# CAN_PHY.net
KiCad netlist of a schematic drawn in Altium Designer
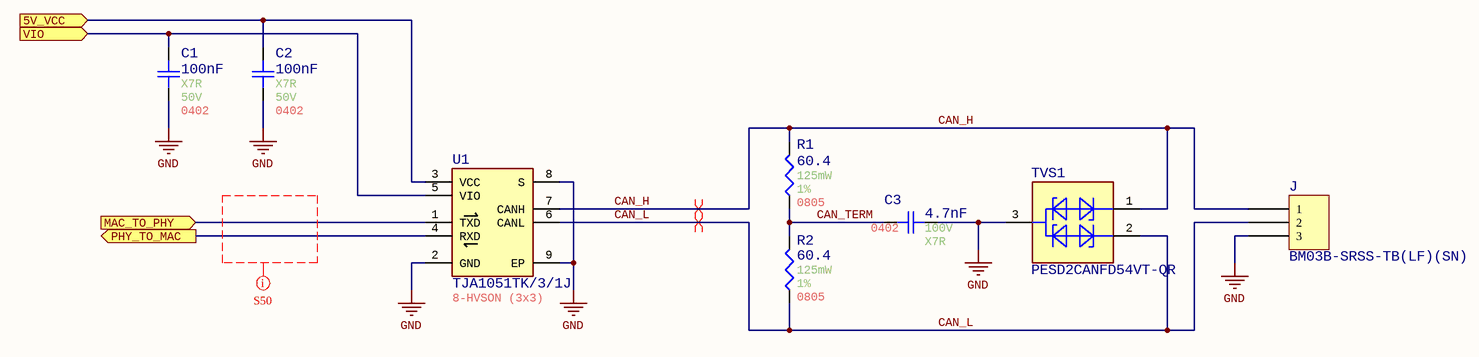
[diagram p0: CAN_PHY.SchDoc]

(export (version "E")
  (design (tool "Eeschema 10.0.6"))
  (components
    (comp (ref "C1")
      (value "100nF")
      (footprint "Generic 0402 capacitor")
      (fields
        (field (name "TEMPERATURE COEFFICIENT") "X7R")
        (field (name "VOLTAGE RATING") "50V")
        (field (name "CASE/PACKAGE") "0402")
        (field (name "TOLERANCE") "10%")
        (field (name "Comment") "GRT155R71H104KE01D")
      )
      (libsource (lib "Raise Robotics") (part "Unpolarized Capacitor"))
    )
    (comp (ref "C2")
      (value "100nF")
      (footprint "Generic 0402 capacitor")
      (fields
        (field (name "TEMPERATURE COEFFICIENT") "X7R")
        (field (name "VOLTAGE RATING") "50V")
        (field (name "CASE/PACKAGE") "0402")
        (field (name "TOLERANCE") "10%")
        (field (name "Comment") "GRT155R71H104KE01D")
      )
      (libsource (lib "Raise Robotics") (part "Unpolarized Capacitor"))
    )
    (comp (ref "C3")
      (value "4.7nF")
      (footprint "Generic 0402 capacitor")
      (fields
        (field (name "TEMPERATURE COEFFICIENT") "X7R")
        (field (name "VOLTAGE RATING") "100V")
        (field (name "CASE/PACKAGE") "0402")
        (field (name "TOLERANCE") "10%")
        (field (name "Comment") "GCM155R72A472KA37D")
      )
      (libsource (lib "Raise Robotics") (part "Unpolarized Capacitor"))
    )
    (comp (ref "J")
      (value "BM03B-SRSS-TB(LF)(SN)")
      (footprint "JST BM03B-SRSS-TB")
      (description "CONN HEADER SMD 3POS 1MM")
      (fields (field (name "MANUFACTURER") "JST Sales America Inc."))
      (libsource (lib "Celestial Altium Library - altium_library") (part "3 Pin"))
    )
    (comp (ref "R1")
      (value "60.4")
      (footprint "0805 Resistor")
      (description "Res 60.4 Ohm 1% 1/8W 0805")
      (fields
        (field (name "POWER") "125mW")
        (field (name "TOLERANCE") "1%")
        (field (name "CASE/PACKAGE") "0805")
        (field (name "MANUFACTURER PART NUMBER") "TFA0805R60R4F-T5")
      )
      (libsource (lib "Raise Robotics") (part "Resistor"))
    )
    (comp (ref "R2")
      (value "60.4")
      (footprint "0805 Resistor")
      (description "Res 60.4 Ohm 1% 1/8W 0805")
      (fields
        (field (name "POWER") "125mW")
        (field (name "TOLERANCE") "1%")
        (field (name "CASE/PACKAGE") "0805")
        (field (name "MANUFACTURER PART NUMBER") "TFA0805R60R4F-T5")
      )
      (libsource (lib "Raise Robotics") (part "Resistor"))
    )
    (comp (ref "TVS1")
      (value "PESD2CANFD54VT-QR")
      (footprint "PESD2CANFD54VT-QR")
      (description "ESD protection for in-vehicle networks")
      (libsource (lib "Raise Robotics") (part "PESD2CANFD54VT-QRVS"))
    )
    (comp (ref "U1")
      (value "TJA1051TK/3/1J")
      (footprint "TJA1044xxK")
      (description "Interface Circuit, PDSO8")
      (fields (field (name "CASE/PACKAGE") "8-HVSON (3x3)"))
      (libsource (lib "Raise Robotics") (part "TJA1044"))
    )
  )
  (nets
    (net (code "1") (name "/5V_VCC") (class "Default")
      (node (ref "C2") (pin "1") (pinfunction "1_1") (pintype "passive"))
      (node (ref "U1") (pin "3") (pinfunction "VCC_3") (pintype "passive"))
    )
    (net (code "2") (name "/CAN_H") (class "Default")
      (node (ref "J") (pin "1") (pinfunction "1_1") (pintype "passive"))
      (node (ref "R1") (pin "2") (pinfunction "2_2") (pintype "passive"))
      (node (ref "TVS1") (pin "1") (pinfunction "K1_1") (pintype "passive"))
      (node (ref "U1") (pin "7") (pinfunction "CANH_7") (pintype "passive"))
    )
    (net (code "3") (name "/CAN_L") (class "Default")
      (node (ref "J") (pin "2") (pinfunction "2_2") (pintype "passive"))
      (node (ref "R2") (pin "1") (pinfunction "1_1") (pintype "passive"))
      (node (ref "TVS1") (pin "2") (pinfunction "K2_2") (pintype "passive"))
      (node (ref "U1") (pin "6") (pinfunction "CANL_6") (pintype "passive"))
    )
    (net (code "4") (name "/CAN_TERM") (class "Default")
      (node (ref "C3") (pin "2") (pinfunction "2_2") (pintype "passive"))
      (node (ref "R1") (pin "1") (pinfunction "1_1") (pintype "passive"))
      (node (ref "R2") (pin "2") (pinfunction "2_2") (pintype "passive"))
    )
    (net (code "5") (name "/MAC_TO_PHY") (class "Default")
      (node (ref "U1") (pin "1") (pinfunction "TXD_1") (pintype "passive"))
    )
    (net (code "6") (name "/PHY_TO_MAC") (class "Default")
      (node (ref "U1") (pin "4") (pinfunction "RXD_4") (pintype "passive"))
    )
    (net (code "7") (name "/VIO") (class "Default")
      (node (ref "C1") (pin "1") (pinfunction "1_1") (pintype "passive"))
      (node (ref "U1") (pin "5") (pinfunction "VIO_5") (pintype "passive"))
    )
    (net (code "8") (name "GND") (class "Default")
      (node (ref "C1") (pin "2") (pinfunction "2_2") (pintype "passive"))
      (node (ref "C2") (pin "2") (pinfunction "2_2") (pintype "passive"))
      (node (ref "C3") (pin "1") (pinfunction "1_1") (pintype "passive"))
      (node (ref "J") (pin "3") (pinfunction "3_3") (pintype "passive"))
      (node (ref "TVS1") (pin "3") (pinfunction "CC_3") (pintype "passive"))
      (node (ref "U1") (pin "2") (pinfunction "GND_2") (pintype "passive"))
      (node (ref "U1") (pin "8") (pinfunction "S_8") (pintype "passive"))
      (node (ref "U1") (pin "9") (pinfunction "EP_9") (pintype "passive"))
    )
  )
)
